# smartIndoor.net
KiCad netlist of a schematic drawn in EAGLE
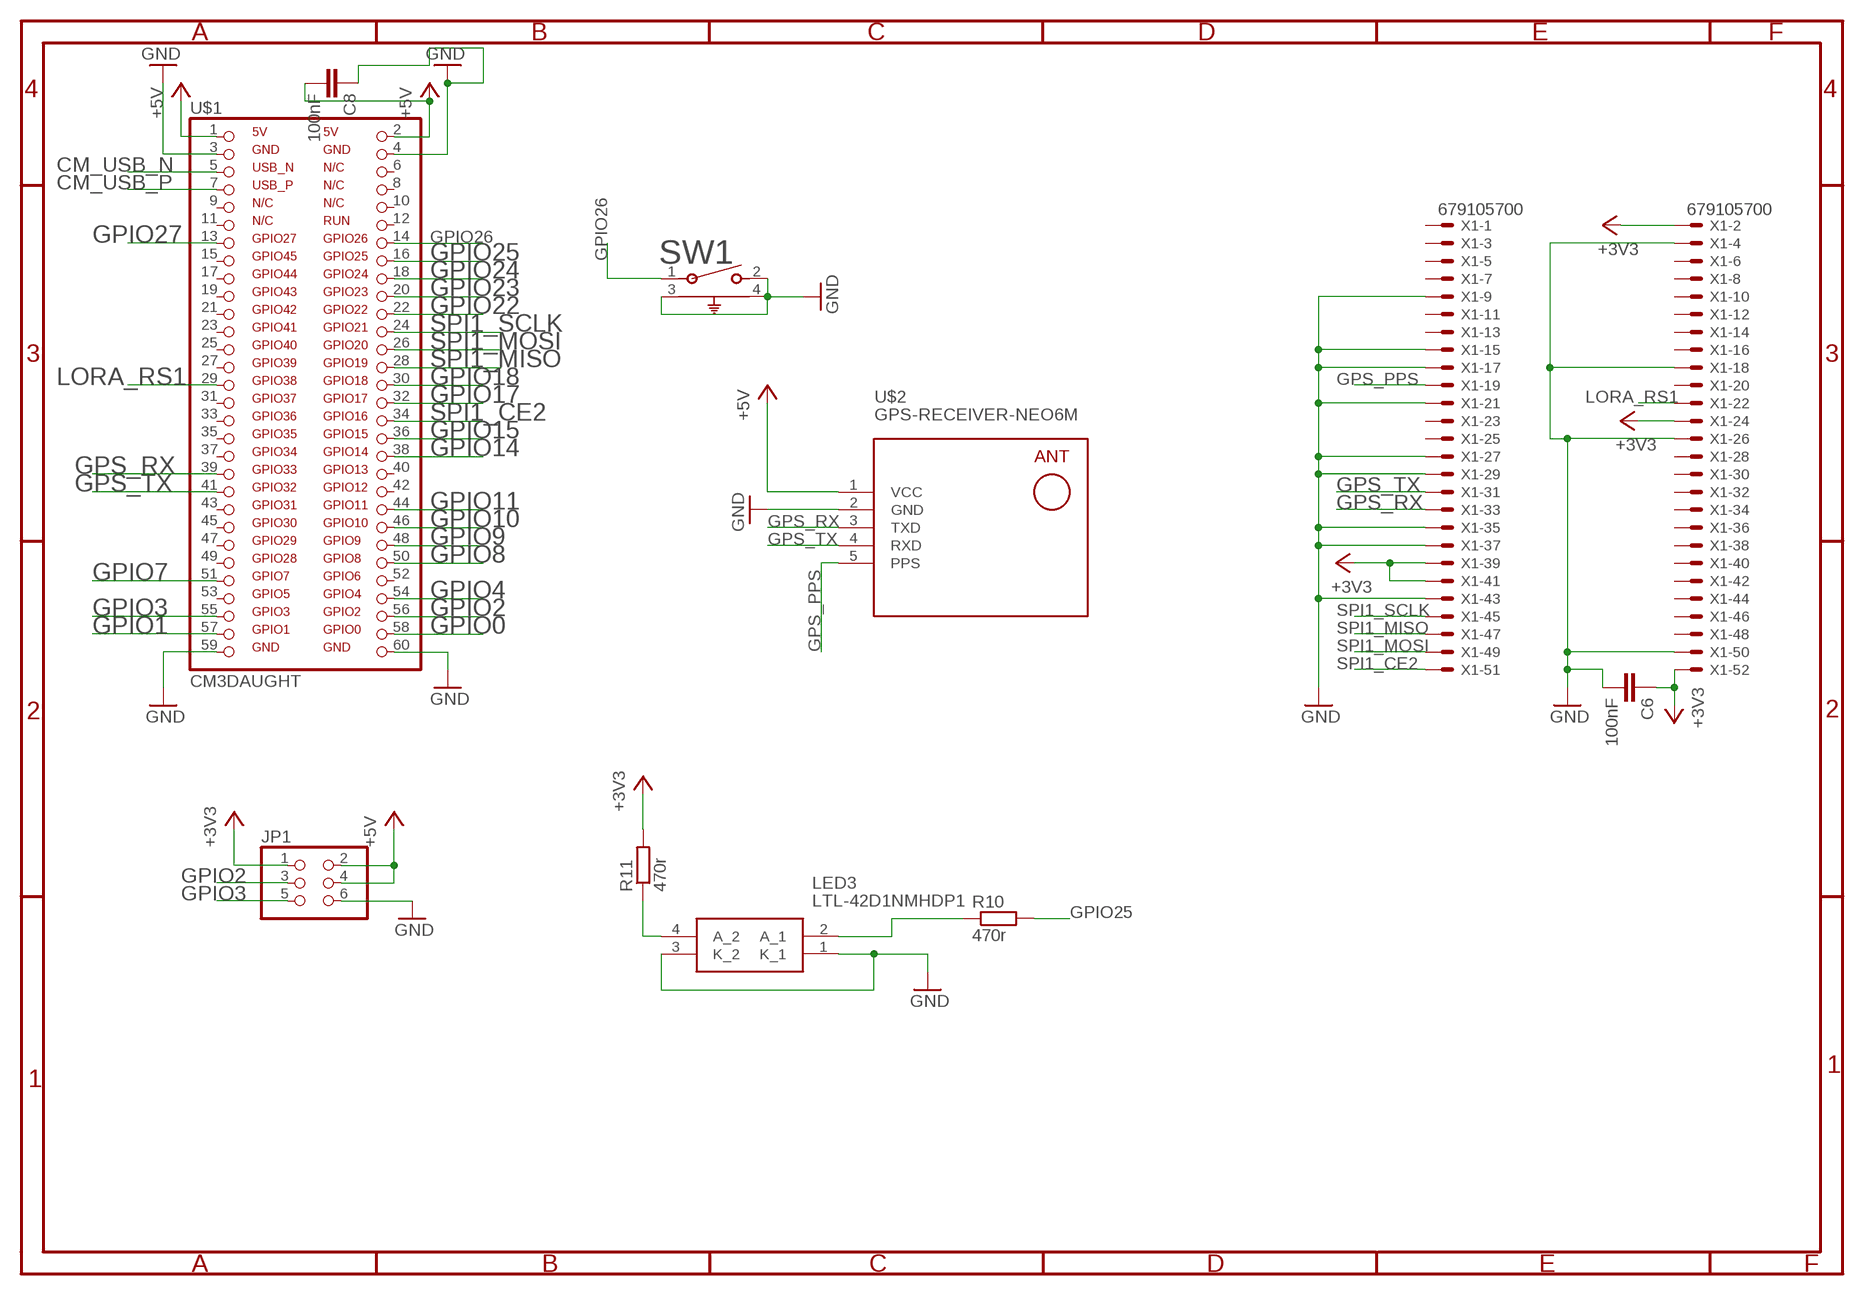
[diagram p0: schematic, sheet 1]
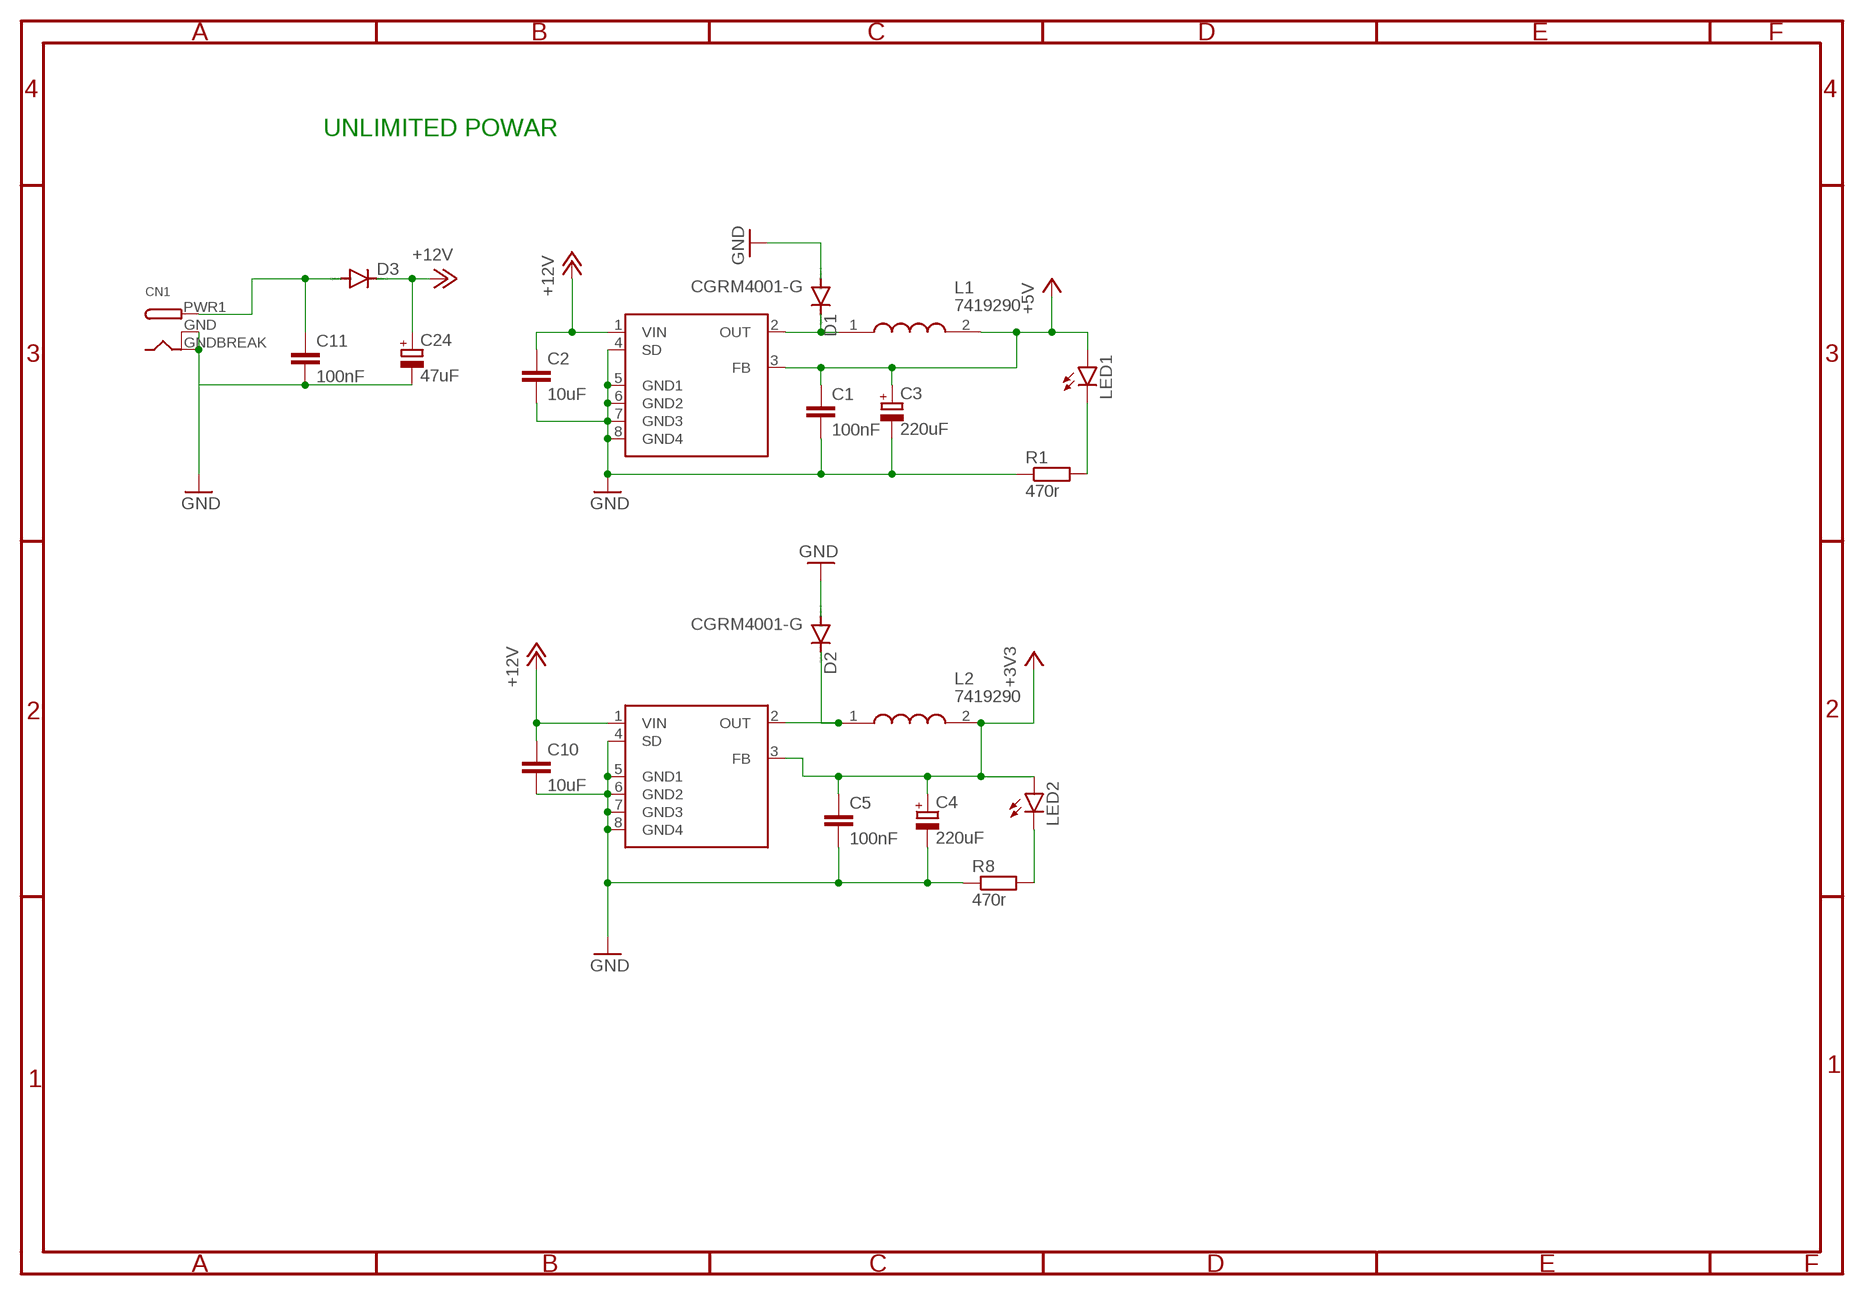
[diagram p1: schematic, sheet 2]
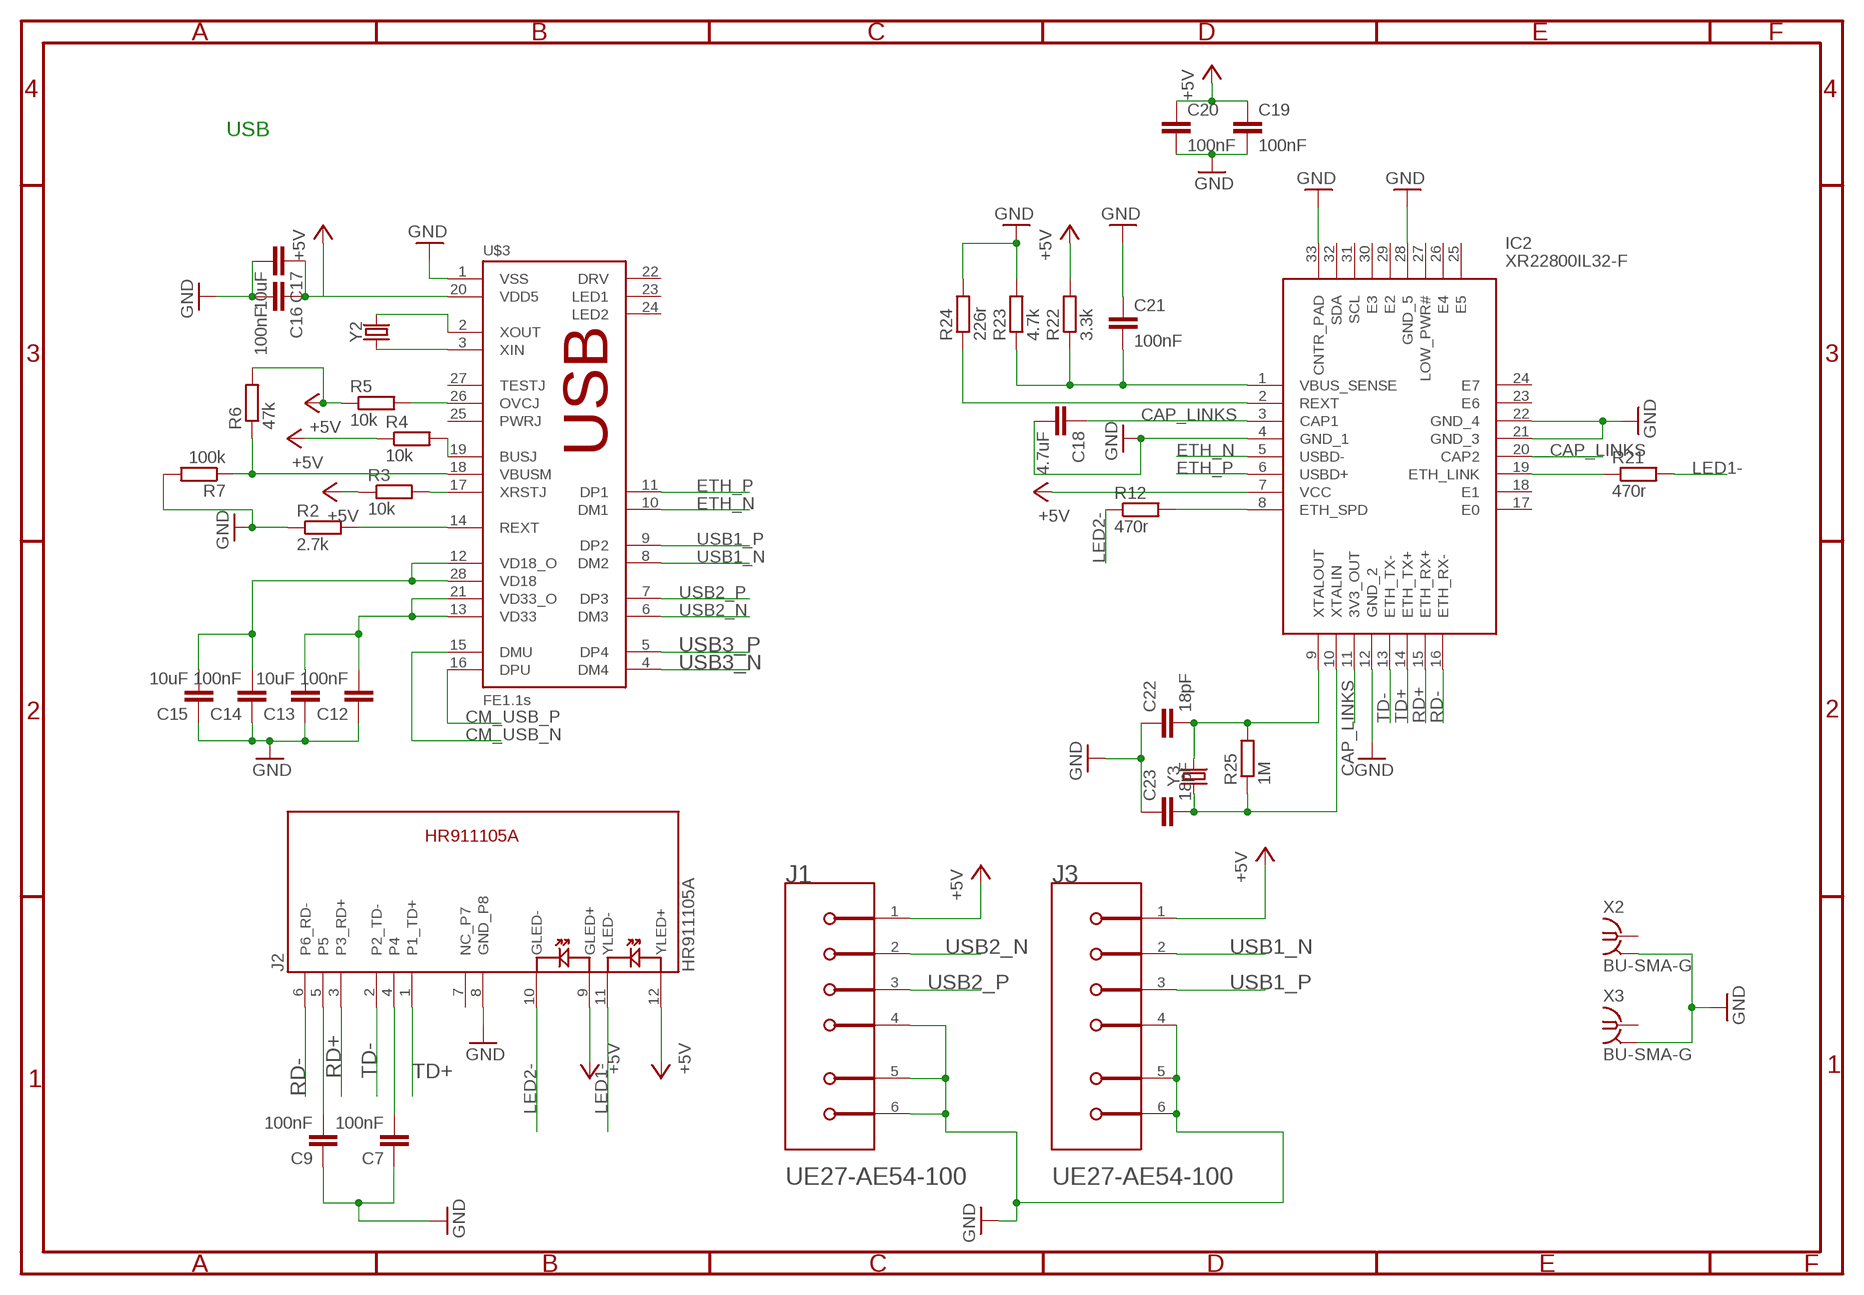
[diagram p2: schematic, sheet 3]

(export (version "E")
  (design (tool "Eeschema 10.0.6"))
  (components
    (comp (ref "C6")
      (value "100nF")
      (footprint "eagle-import:C0603")
      (libsource (lib "eagle-import") (part "C-EUC0603"))
    )
    (comp (ref "C8")
      (value "100nF")
      (footprint "eagle-import:C0603")
      (libsource (lib "eagle-import") (part "C-EUC0603"))
    )
    (comp (ref "JP1")
      (value "PINHD-2X3")
      (footprint "eagle-import:2X03")
      (libsource (lib "eagle-import") (part "PINHD-2X3"))
    )
    (comp (ref "LED3")
      (value "LTL-42D1NMHDP1")
      (footprint "eagle-import:LTL42D1NMHDP1")
      (fields (field (name "MOUSER_PART_NUMBER") "859-LTL-42D1NMHDP1"))
      (libsource (lib "eagle-import") (part "LTL-42D1NMHDP1"))
    )
    (comp (ref "R10")
      (value "470r")
      (footprint "eagle-import:R0603")
      (libsource (lib "eagle-import") (part "R-EU_R0603"))
    )
    (comp (ref "R11")
      (value "470r")
      (footprint "eagle-import:R0603")
      (libsource (lib "eagle-import") (part "R-EU_R0603"))
    )
    (comp (ref "SW1")
      (value "1825027-8")
      (footprint "eagle-import:SW2_1825027-C_TEC")
      (fields (field (name "COPYRIGHT") "Copyright (C) 2016 Accelerated Designs. All rights reserved"))
      (libsource (lib "eagle-import") (part "1825027-8"))
    )
    (comp (ref "U$1")
      (value "CM3DAUGHT")
      (footprint "eagle-import:2X30")
      (libsource (lib "eagle-import") (part "CM3DAUGHT"))
    )
    (comp (ref "U$2")
      (value "GPS-RECEIVER-NEO6M")
      (footprint "eagle-import:GPS-RECEIVER-NEO6M")
      (libsource (lib "eagle-import") (part "GPS-RECEIVER-NEO6M"))
    )
    (comp (ref "X1")
      (value "679105700")
      (footprint "eagle-import:679105700")
      (fields (field (name "MPN") "67910-5700"))
      (libsource (lib "eagle-import") (part "679105700"))
    )
    (comp (ref "C7")
      (value "100nF")
      (footprint "eagle-import:C0603")
      (libsource (lib "eagle-import") (part "C-EUC0603"))
    )
    (comp (ref "C9")
      (value "100nF")
      (footprint "eagle-import:C0603")
      (libsource (lib "eagle-import") (part "C-EUC0603"))
    )
    (comp (ref "C12")
      (value "100nF")
      (footprint "eagle-import:C0603")
      (libsource (lib "eagle-import") (part "C-EUC0603"))
    )
    (comp (ref "C13")
      (value "10uF")
      (footprint "eagle-import:C0603")
      (libsource (lib "eagle-import") (part "C-EUC0603"))
    )
    (comp (ref "C14")
      (value "100nF")
      (footprint "eagle-import:C0603")
      (libsource (lib "eagle-import") (part "C-EUC0603"))
    )
    (comp (ref "C15")
      (value "10uF")
      (footprint "eagle-import:C0603")
      (libsource (lib "eagle-import") (part "C-EUC0603"))
    )
    (comp (ref "C16")
      (value "100nF")
      (footprint "eagle-import:C0603")
      (libsource (lib "eagle-import") (part "C-EUC0603"))
    )
    (comp (ref "C17")
      (value "10uF")
      (footprint "eagle-import:C0603")
      (libsource (lib "eagle-import") (part "C-EUC0603"))
    )
    (comp (ref "C18")
      (value "4.7uF")
      (footprint "eagle-import:C0603")
      (libsource (lib "eagle-import") (part "C-EUC0603"))
    )
    (comp (ref "C19")
      (value "100nF")
      (footprint "eagle-import:C0603")
      (libsource (lib "eagle-import") (part "C-EUC0603"))
    )
    (comp (ref "C20")
      (value "100nF")
      (footprint "eagle-import:C0603")
      (libsource (lib "eagle-import") (part "C-EUC0603"))
    )
    (comp (ref "C21")
      (value "100nF")
      (footprint "eagle-import:C0603")
      (libsource (lib "eagle-import") (part "C-EUC0603"))
    )
    (comp (ref "C22")
      (value "18pF")
      (footprint "eagle-import:C0603")
      (libsource (lib "eagle-import") (part "C-EUC0603"))
    )
    (comp (ref "C23")
      (value "18pF")
      (footprint "eagle-import:C0603")
      (libsource (lib "eagle-import") (part "C-EUC0603"))
    )
    (comp (ref "IC2")
      (value "XR22800IL32-F")
      (footprint "eagle-import:QFN50P500X500X100-33N")
      (fields (field (name "MOUSER_PART_NUMBER") "701-22800IL32-F"))
      (libsource (lib "eagle-import") (part "XR22800IL32-F"))
    )
    (comp (ref "J1")
      (value "AMPHENOL_UE27-AE54-100AMPHENOL_UE27-AE54-100_0_0")
      (footprint "eagle-import:AMPHENOL_UE27-AE54-100_0")
      (fields
        (field (name "DIGIKEY_PART_NUMBER") "UE27AE54100-ND")
        (field (name "MF") "Amphenol")
        (field (name "MOUSER_PART_NUMBER") "523-UE27-AE54-100")
      )
      (libsource (lib "eagle-import") (part "AMPHENOL_UE27-AE54-100AMPHENOL_UE27-AE54-100_0_0"))
    )
    (comp (ref "J2")
      (value "HR911105A")
      (footprint "eagle-import:HR911105A")
      (libsource (lib "eagle-import") (part "HR911105A"))
    )
    (comp (ref "J3")
      (value "AMPHENOL_UE27-AE54-100AMPHENOL_UE27-AE54-100_0_0")
      (footprint "eagle-import:AMPHENOL_UE27-AE54-100_0")
      (fields
        (field (name "DIGIKEY_PART_NUMBER") "UE27AE54100-ND")
        (field (name "MF") "Amphenol")
        (field (name "MOUSER_PART_NUMBER") "523-UE27-AE54-100")
      )
      (libsource (lib "eagle-import") (part "AMPHENOL_UE27-AE54-100AMPHENOL_UE27-AE54-100_0_0"))
    )
    (comp (ref "R2")
      (value "2.7k")
      (footprint "eagle-import:R0603")
      (libsource (lib "eagle-import") (part "R-EU_R0603"))
    )
    (comp (ref "R3")
      (value "10k")
      (footprint "eagle-import:R0603")
      (libsource (lib "eagle-import") (part "R-EU_R0603"))
    )
    (comp (ref "R4")
      (value "10k")
      (footprint "eagle-import:R0603")
      (libsource (lib "eagle-import") (part "R-EU_R0603"))
    )
    (comp (ref "R5")
      (value "10k")
      (footprint "eagle-import:R0603")
      (libsource (lib "eagle-import") (part "R-EU_R0603"))
    )
    (comp (ref "R6")
      (value "47k")
      (footprint "eagle-import:R0603")
      (libsource (lib "eagle-import") (part "R-EU_R0603"))
    )
    (comp (ref "R7")
      (value "100k")
      (footprint "eagle-import:R0603")
      (libsource (lib "eagle-import") (part "R-EU_R0603"))
    )
    (comp (ref "R12")
      (value "470r")
      (footprint "eagle-import:R0603")
      (libsource (lib "eagle-import") (part "R-EU_R0603"))
    )
    (comp (ref "R21")
      (value "470r")
      (footprint "eagle-import:R0603")
      (libsource (lib "eagle-import") (part "R-EU_R0603"))
    )
    (comp (ref "R22")
      (value "3.3k")
      (footprint "eagle-import:R0603")
      (libsource (lib "eagle-import") (part "R-EU_R0603"))
    )
    (comp (ref "R23")
      (value "4.7k")
      (footprint "eagle-import:R0603")
      (libsource (lib "eagle-import") (part "R-EU_R0603"))
    )
    (comp (ref "R24")
      (value "226r")
      (footprint "eagle-import:R0603")
      (libsource (lib "eagle-import") (part "R-EU_R0603"))
    )
    (comp (ref "R25")
      (value "1M")
      (footprint "eagle-import:R0603")
      (libsource (lib "eagle-import") (part "R-EU_R0603"))
    )
    (comp (ref "U$3")
      (value "FE1.1S")
      (footprint "eagle-import:FE1.1S_SSOP-28")
      (libsource (lib "eagle-import") (part "FE1.1S"))
    )
    (comp (ref "X2")
      (value "BU-SMA-G")
      (footprint "eagle-import:BU-SMA-G")
      (libsource (lib "eagle-import") (part "BU-SMA-G"))
    )
    (comp (ref "X3")
      (value "BU-SMA-G")
      (footprint "eagle-import:BU-SMA-G")
      (libsource (lib "eagle-import") (part "BU-SMA-G"))
    )
    (comp (ref "Y2")
      (value "12mHZ")
      (footprint "eagle-import:HC49UP")
      (libsource (lib "eagle-import") (part "CRYSTALSMD-HC49UP"))
    )
    (comp (ref "Y3")
      (value "25Mhz")
      (footprint "eagle-import:HC49UP")
      (libsource (lib "eagle-import") (part "CRYSTALSMD-HC49UP"))
    )
    (comp (ref "C1")
      (value "100nF")
      (footprint "eagle-import:C0603")
      (libsource (lib "eagle-import") (part "C-EUC0603"))
    )
    (comp (ref "C2")
      (value "10uF")
      (footprint "eagle-import:C0603")
      (libsource (lib "eagle-import") (part "C-EUC0603"))
    )
    (comp (ref "C3")
      (value "220uF")
      (footprint "eagle-import:PANASONIC_D")
      (libsource (lib "eagle-import") (part "CPOL-EUD"))
    )
    (comp (ref "C4")
      (value "220uF")
      (footprint "eagle-import:PANASONIC_D")
      (libsource (lib "eagle-import") (part "CPOL-EUD"))
    )
    (comp (ref "C5")
      (value "100nF")
      (footprint "eagle-import:C0603")
      (libsource (lib "eagle-import") (part "C-EUC0603"))
    )
    (comp (ref "C10")
      (value "10uF")
      (footprint "eagle-import:C0603")
      (libsource (lib "eagle-import") (part "C-EUC0603"))
    )
    (comp (ref "C11")
      (value "100nF")
      (footprint "eagle-import:C0603")
      (libsource (lib "eagle-import") (part "C-EUC0603"))
    )
    (comp (ref "C24")
      (value "47uF")
      (footprint "eagle-import:PANASONIC_D")
      (libsource (lib "eagle-import") (part "CPOL-EUD"))
    )
    (comp (ref "CN1")
      (value "DCBARRELSMT")
      (footprint "eagle-import:DCJACK_2MM_SMT")
      (libsource (lib "eagle-import") (part "DCBARRELSMT"))
    )
    (comp (ref "D1")
      (value "CGRM4001-G")
      (footprint "eagle-import:SOD-123_MINI-SMA")
      (libsource (lib "eagle-import") (part "CGRM400-G1"))
    )
    (comp (ref "D2")
      (value "CGRM4001-G")
      (footprint "eagle-import:SOD-123_MINI-SMA")
      (libsource (lib "eagle-import") (part "CGRM400-G1"))
    )
    (comp (ref "D3")
      (value "DIODE-SMB")
      (footprint "eagle-import:SMB")
      (libsource (lib "eagle-import") (part "DIODE-SMB"))
    )
    (comp (ref "L1")
      (value "7419290")
      (footprint "eagle-import:INDPM115100X410N")
      (libsource (lib "eagle-import") (part "7419290"))
    )
    (comp (ref "L2")
      (value "7419290")
      (footprint "eagle-import:INDPM115100X410N")
      (libsource (lib "eagle-import") (part "7419290"))
    )
    (comp (ref "LED1")
      (value "LEDCHIP-LED0603")
      (footprint "eagle-import:CHIP-LED0603")
      (libsource (lib "eagle-import") (part "LEDCHIP-LED0603"))
    )
    (comp (ref "LED2")
      (value "LEDCHIP-LED0603")
      (footprint "eagle-import:CHIP-LED0603")
      (libsource (lib "eagle-import") (part "LEDCHIP-LED0603"))
    )
    (comp (ref "R1")
      (value "470r")
      (footprint "eagle-import:R0603")
      (libsource (lib "eagle-import") (part "R-EU_R0603"))
    )
    (comp (ref "R8")
      (value "470r")
      (footprint "eagle-import:R0603")
      (libsource (lib "eagle-import") (part "R-EU_R0603"))
    )
    (comp (ref "U1")
      (value "AP1509")
      (footprint "eagle-import:SO08")
      (libsource (lib "eagle-import") (part "AP1509"))
    )
    (comp (ref "U2")
      (value "AP1509")
      (footprint "eagle-import:SO08")
      (libsource (lib "eagle-import") (part "AP1509"))
    )
  )
  (nets
    (net (code "1") (name "+3V3") (class "Default")
      (node (ref "C4") (pin "+") (pinfunction "+_+") (pintype "passive"))
      (node (ref "C5") (pin "1") (pinfunction "1_1") (pintype "passive"))
      (node (ref "C6") (pin "1") (pinfunction "1_1") (pintype "passive"))
      (node (ref "JP1") (pin "1") (pinfunction "1_1") (pintype "passive"))
      (node (ref "L2") (pin "2") (pinfunction "2_2") (pintype "bidirectional"))
      (node (ref "LED2") (pin "A") (pinfunction "A_A") (pintype "passive"))
      (node (ref "R11") (pin "2") (pinfunction "2_2") (pintype "passive"))
      (node (ref "U2") (pin "3") (pinfunction "FB_3") (pintype "input"))
      (node (ref "X1") (pin "2") (pinfunction "S_2") (pintype "passive"))
      (node (ref "X1") (pin "24") (pinfunction "S_24") (pintype "passive"))
      (node (ref "X1") (pin "39") (pinfunction "S_39") (pintype "passive"))
      (node (ref "X1") (pin "41") (pinfunction "S_41") (pintype "passive"))
      (node (ref "X1") (pin "52") (pinfunction "S_52") (pintype "passive"))
    )
    (net (code "2") (name "+5V") (class "Default")
      (node (ref "C1") (pin "1") (pinfunction "1_1") (pintype "passive"))
      (node (ref "C16") (pin "1") (pinfunction "1_1") (pintype "passive"))
      (node (ref "C17") (pin "1") (pinfunction "1_1") (pintype "passive"))
      (node (ref "C19") (pin "1") (pinfunction "1_1") (pintype "passive"))
      (node (ref "C20") (pin "1") (pinfunction "1_1") (pintype "passive"))
      (node (ref "C3") (pin "+") (pinfunction "+_+") (pintype "passive"))
      (node (ref "C8") (pin "2") (pinfunction "2_2") (pintype "passive"))
      (node (ref "IC2") (pin "7") (pinfunction "VCC_7") (pintype "bidirectional"))
      (node (ref "J1") (pin "1") (pinfunction "1_1") (pintype "passive"))
      (node (ref "J2") (pin "12") (pinfunction "YLED+_12") (pintype "bidirectional"))
      (node (ref "J2") (pin "9") (pinfunction "GLED+_9") (pintype "bidirectional"))
      (node (ref "J3") (pin "1") (pinfunction "1_1") (pintype "passive"))
      (node (ref "JP1") (pin "2") (pinfunction "2_2") (pintype "passive"))
      (node (ref "JP1") (pin "4") (pinfunction "4_4") (pintype "passive"))
      (node (ref "L1") (pin "2") (pinfunction "2_2") (pintype "bidirectional"))
      (node (ref "LED1") (pin "A") (pinfunction "A_A") (pintype "passive"))
      (node (ref "R22") (pin "2") (pinfunction "2_2") (pintype "passive"))
      (node (ref "R3") (pin "1") (pinfunction "1_1") (pintype "passive"))
      (node (ref "R4") (pin "1") (pinfunction "1_1") (pintype "passive"))
      (node (ref "R5") (pin "1") (pinfunction "1_1") (pintype "passive"))
      (node (ref "R6") (pin "2") (pinfunction "2_2") (pintype "passive"))
      (node (ref "U$1") (pin "1") (pinfunction "5V_1") (pintype "power_in"))
      (node (ref "U$1") (pin "2") (pinfunction "5V_2") (pintype "power_in"))
      (node (ref "U$2") (pin "1") (pinfunction "VCC_1") (pintype "bidirectional"))
      (node (ref "U$3") (pin "20") (pinfunction "VDD5_20") (pintype "bidirectional"))
      (node (ref "U1") (pin "3") (pinfunction "FB_3") (pintype "input"))
    )
    (net (code "3") (name "+12V") (class "Default")
      (node (ref "C10") (pin "1") (pinfunction "1_1") (pintype "passive"))
      (node (ref "C2") (pin "1") (pinfunction "1_1") (pintype "passive"))
      (node (ref "C24") (pin "+") (pinfunction "+_+") (pintype "passive"))
      (node (ref "D3") (pin "C") (pinfunction "C_C") (pintype "passive"))
      (node (ref "U1") (pin "1") (pinfunction "VIN_1") (pintype "power_in"))
      (node (ref "U2") (pin "1") (pinfunction "VIN_1") (pintype "power_in"))
    )
    (net (code "4") (name "CAP_LINKS") (class "Default")
      (node (ref "C18") (pin "1") (pinfunction "1_1") (pintype "passive"))
      (node (ref "IC2") (pin "11") (pinfunction "3V3_OUT_11") (pintype "bidirectional"))
      (node (ref "IC2") (pin "20") (pinfunction "CAP2_20") (pintype "bidirectional"))
      (node (ref "IC2") (pin "3") (pinfunction "CAP1_3") (pintype "bidirectional"))
    )
    (net (code "5") (name "CM_USB_N") (class "Default")
      (node (ref "U$1") (pin "5") (pinfunction "USB_N_5") (pintype "passive"))
      (node (ref "U$3") (pin "15") (pinfunction "DMU_15") (pintype "bidirectional"))
    )
    (net (code "6") (name "CM_USB_P") (class "Default")
      (node (ref "U$1") (pin "7") (pinfunction "USB_P_7") (pintype "passive"))
      (node (ref "U$3") (pin "16") (pinfunction "DPU_16") (pintype "bidirectional"))
    )
    (net (code "7") (name "ETH_N") (class "Default")
      (node (ref "IC2") (pin "5") (pinfunction "USBD-_5") (pintype "bidirectional"))
      (node (ref "U$3") (pin "10") (pinfunction "DM1_10") (pintype "bidirectional"))
    )
    (net (code "8") (name "ETH_P") (class "Default")
      (node (ref "IC2") (pin "6") (pinfunction "USBD+_6") (pintype "bidirectional"))
      (node (ref "U$3") (pin "11") (pinfunction "DP1_11") (pintype "bidirectional"))
    )
    (net (code "9") (name "GND") (class "Default")
      (node (ref "C1") (pin "2") (pinfunction "2_2") (pintype "passive"))
      (node (ref "C10") (pin "2") (pinfunction "2_2") (pintype "passive"))
      (node (ref "C11") (pin "2") (pinfunction "2_2") (pintype "passive"))
      (node (ref "C12") (pin "1") (pinfunction "1_1") (pintype "passive"))
      (node (ref "C13") (pin "1") (pinfunction "1_1") (pintype "passive"))
      (node (ref "C14") (pin "1") (pinfunction "1_1") (pintype "passive"))
      (node (ref "C15") (pin "1") (pinfunction "1_1") (pintype "passive"))
      (node (ref "C16") (pin "2") (pinfunction "2_2") (pintype "passive"))
      (node (ref "C17") (pin "2") (pinfunction "2_2") (pintype "passive"))
      (node (ref "C18") (pin "2") (pinfunction "2_2") (pintype "passive"))
      (node (ref "C19") (pin "2") (pinfunction "2_2") (pintype "passive"))
      (node (ref "C2") (pin "2") (pinfunction "2_2") (pintype "passive"))
      (node (ref "C20") (pin "2") (pinfunction "2_2") (pintype "passive"))
      (node (ref "C21") (pin "1") (pinfunction "1_1") (pintype "passive"))
      (node (ref "C22") (pin "1") (pinfunction "1_1") (pintype "passive"))
      (node (ref "C23") (pin "1") (pinfunction "1_1") (pintype "passive"))
      (node (ref "C24") (pin "-") (pinfunction "-_-") (pintype "passive"))
      (node (ref "C3") (pin "-") (pinfunction "-_-") (pintype "passive"))
      (node (ref "C4") (pin "-") (pinfunction "-_-") (pintype "passive"))
      (node (ref "C5") (pin "2") (pinfunction "2_2") (pintype "passive"))
      (node (ref "C6") (pin "2") (pinfunction "2_2") (pintype "passive"))
      (node (ref "C7") (pin "1") (pinfunction "1_1") (pintype "passive"))
      (node (ref "C8") (pin "1") (pinfunction "1_1") (pintype "passive"))
      (node (ref "C9") (pin "1") (pinfunction "1_1") (pintype "passive"))
      (node (ref "CN1") (pin "GND") (pinfunction "GNDBREAK_GND") (pintype "power_in"))
      (node (ref "CN1") (pin "GNDBREAK") (pinfunction "GND_GNDBREAK") (pintype "power_in"))
      (node (ref "D1") (pin "A") (pinfunction "A_A") (pintype "passive"))
      (node (ref "D2") (pin "A") (pinfunction "A_A") (pintype "passive"))
      (node (ref "IC2") (pin "12") (pinfunction "GND_2_12") (pintype "bidirectional"))
      (node (ref "IC2") (pin "21") (pinfunction "GND_3_21") (pintype "bidirectional"))
      (node (ref "IC2") (pin "22") (pinfunction "GND_4_22") (pintype "bidirectional"))
      (node (ref "IC2") (pin "28") (pinfunction "GND_5_28") (pintype "bidirectional"))
      (node (ref "IC2") (pin "33") (pinfunction "CNTR_PAD_33") (pintype "bidirectional"))
      (node (ref "IC2") (pin "4") (pinfunction "GND_1_4") (pintype "bidirectional"))
      (node (ref "J1") (pin "4") (pinfunction "4_4") (pintype "passive"))
      (node (ref "J1") (pin "5") (pinfunction "MNT_1_5") (pintype "passive"))
      (node (ref "J1") (pin "6") (pinfunction "MNT_2_6") (pintype "passive"))
      (node (ref "J2") (pin "8") (pinfunction "GND_P8_8") (pintype "bidirectional"))
      (node (ref "J3") (pin "4") (pinfunction "4_4") (pintype "passive"))
      (node (ref "J3") (pin "5") (pinfunction "MNT_1_5") (pintype "passive"))
      (node (ref "J3") (pin "6") (pinfunction "MNT_2_6") (pintype "passive"))
      (node (ref "JP1") (pin "6") (pinfunction "6_6") (pintype "passive"))
      (node (ref "LED3") (pin "1") (pinfunction "K_1_1") (pintype "bidirectional"))
      (node (ref "LED3") (pin "3") (pinfunction "K_2_3") (pintype "bidirectional"))
      (node (ref "R1") (pin "1") (pinfunction "1_1") (pintype "passive"))
      (node (ref "R2") (pin "1") (pinfunction "1_1") (pintype "passive"))
      (node (ref "R23") (pin "2") (pinfunction "2_2") (pintype "passive"))
      (node (ref "R24") (pin "2") (pinfunction "2_2") (pintype "passive"))
      (node (ref "R7") (pin "2") (pinfunction "2_2") (pintype "passive"))
      (node (ref "R8") (pin "1") (pinfunction "1_1") (pintype "passive"))
      (node (ref "SW1") (pin "2") (pinfunction "2_2") (pintype "passive"))
      (node (ref "SW1") (pin "3") (pinfunction "3_3") (pintype "passive"))
      (node (ref "SW1") (pin "4") (pinfunction "4_4") (pintype "passive"))
      (node (ref "U$1") (pin "3") (pinfunction "GND_3") (pintype "power_in"))
      (node (ref "U$1") (pin "4") (pinfunction "GND_4") (pintype "power_in"))
      (node (ref "U$1") (pin "59") (pinfunction "GND_59") (pintype "power_in"))
      (node (ref "U$1") (pin "60") (pinfunction "GND_60") (pintype "power_in"))
      (node (ref "U$2") (pin "2") (pinfunction "GND_2") (pintype "bidirectional"))
      (node (ref "U$3") (pin "1") (pinfunction "VSS_1") (pintype "bidirectional"))
      (node (ref "U1") (pin "4") (pinfunction "SD_4") (pintype "input"))
      (node (ref "U1") (pin "5") (pinfunction "GND1_5") (pintype "power_in"))
      (node (ref "U1") (pin "6") (pinfunction "GND2_6") (pintype "power_in"))
      (node (ref "U1") (pin "7") (pinfunction "GND3_7") (pintype "power_in"))
      (node (ref "U1") (pin "8") (pinfunction "GND4_8") (pintype "power_in"))
      (node (ref "U2") (pin "4") (pinfunction "SD_4") (pintype "input"))
      (node (ref "U2") (pin "5") (pinfunction "GND1_5") (pintype "power_in"))
      (node (ref "U2") (pin "6") (pinfunction "GND2_6") (pintype "power_in"))
      (node (ref "U2") (pin "7") (pinfunction "GND3_7") (pintype "power_in"))
      (node (ref "U2") (pin "8") (pinfunction "GND4_8") (pintype "power_in"))
      (node (ref "X1") (pin "15") (pinfunction "S_15") (pintype "passive"))
      (node (ref "X1") (pin "17") (pinfunction "S_17") (pintype "passive"))
      (node (ref "X1") (pin "18") (pinfunction "S_18") (pintype "passive"))
      (node (ref "X1") (pin "21") (pinfunction "S_21") (pintype "passive"))
      (node (ref "X1") (pin "26") (pinfunction "S_26") (pintype "passive"))
      (node (ref "X1") (pin "27") (pinfunction "S_27") (pintype "passive"))
      (node (ref "X1") (pin "29") (pinfunction "S_29") (pintype "passive"))
      (node (ref "X1") (pin "35") (pinfunction "S_35") (pintype "passive"))
      (node (ref "X1") (pin "37") (pinfunction "S_37") (pintype "passive"))
      (node (ref "X1") (pin "4") (pinfunction "S_4") (pintype "passive"))
      (node (ref "X1") (pin "43") (pinfunction "S_43") (pintype "passive"))
      (node (ref "X1") (pin "50") (pinfunction "S_50") (pintype "passive"))
      (node (ref "X1") (pin "9") (pinfunction "S_9") (pintype "passive"))
      (node (ref "X2") (pin "2") (pinfunction "2_2") (pintype "passive"))
      (node (ref "X2") (pin "3") (pinfunction "2_3") (pintype "passive"))
      (node (ref "X2") (pin "4") (pinfunction "2_4") (pintype "passive"))
      (node (ref "X2") (pin "5") (pinfunction "2_5") (pintype "passive"))
      (node (ref "X3") (pin "2") (pinfunction "2_2") (pintype "passive"))
      (node (ref "X3") (pin "3") (pinfunction "2_3") (pintype "passive"))
      (node (ref "X3") (pin "4") (pinfunction "2_4") (pintype "passive"))
      (node (ref "X3") (pin "5") (pinfunction "2_5") (pintype "passive"))
    )
    (net (code "10") (name "GPIO0") (class "Default")
      (node (ref "U$1") (pin "58") (pinfunction "GPIO0_58") (pintype "passive"))
    )
    (net (code "11") (name "GPIO1") (class "Default")
      (node (ref "U$1") (pin "57") (pinfunction "GPIO1_57") (pintype "passive"))
    )
    (net (code "12") (name "GPIO2") (class "Default")
      (node (ref "JP1") (pin "3") (pinfunction "3_3") (pintype "passive"))
      (node (ref "U$1") (pin "56") (pinfunction "GPIO2_56") (pintype "passive"))
    )
    (net (code "13") (name "GPIO3") (class "Default")
      (node (ref "JP1") (pin "5") (pinfunction "5_5") (pintype "passive"))
      (node (ref "U$1") (pin "55") (pinfunction "GPIO3_55") (pintype "passive"))
    )
    (net (code "14") (name "GPIO4") (class "Default")
      (node (ref "U$1") (pin "54") (pinfunction "GPIO4_54") (pintype "passive"))
    )
    (net (code "15") (name "GPIO7") (class "Default")
      (node (ref "U$1") (pin "51") (pinfunction "GPIO7_51") (pintype "passive"))
    )
    (net (code "16") (name "GPIO8") (class "Default")
      (node (ref "U$1") (pin "50") (pinfunction "GPIO8_50") (pintype "passive"))
    )
    (net (code "17") (name "GPIO9") (class "Default")
      (node (ref "U$1") (pin "48") (pinfunction "GPIO9_48") (pintype "passive"))
    )
    (net (code "18") (name "GPIO10") (class "Default")
      (node (ref "U$1") (pin "46") (pinfunction "GPIO10_46") (pintype "passive"))
    )
    (net (code "19") (name "GPIO11") (class "Default")
      (node (ref "U$1") (pin "44") (pinfunction "GPIO11_44") (pintype "passive"))
    )
    (net (code "20") (name "GPIO14") (class "Default")
      (node (ref "U$1") (pin "38") (pinfunction "GPIO14_38") (pintype "passive"))
    )
    (net (code "21") (name "GPIO15") (class "Default")
      (node (ref "U$1") (pin "36") (pinfunction "GPIO15_36") (pintype "passive"))
    )
    (net (code "22") (name "GPIO17") (class "Default")
      (node (ref "U$1") (pin "32") (pinfunction "GPIO17_32") (pintype "passive"))
    )
    (net (code "23") (name "GPIO18") (class "Default")
      (node (ref "U$1") (pin "30") (pinfunction "GPIO18_30") (pintype "passive"))
    )
    (net (code "24") (name "GPIO22") (class "Default")
      (node (ref "U$1") (pin "22") (pinfunction "GPIO22_22") (pintype "passive"))
    )
    (net (code "25") (name "GPIO23") (class "Default")
      (node (ref "U$1") (pin "20") (pinfunction "GPIO23_20") (pintype "passive"))
    )
    (net (code "26") (name "GPIO24") (class "Default")
      (node (ref "U$1") (pin "18") (pinfunction "GPIO24_18") (pintype "passive"))
    )
    (net (code "27") (name "GPIO25") (class "Default")
      (node (ref "R10") (pin "2") (pinfunction "2_2") (pintype "passive"))
      (node (ref "U$1") (pin "16") (pinfunction "GPIO25_16") (pintype "passive"))
    )
    (net (code "28") (name "GPIO26") (class "Default")
      (node (ref "SW1") (pin "1") (pinfunction "1_1") (pintype "passive"))
      (node (ref "U$1") (pin "14") (pinfunction "GPIO26_14") (pintype "passive"))
    )
    (net (code "29") (name "GPIO27") (class "Default")
      (node (ref "U$1") (pin "13") (pinfunction "GPIO27_13") (pintype "passive"))
    )
    (net (code "30") (name "GPS_PPS") (class "Default")
      (node (ref "U$2") (pin "5") (pinfunction "PPS_5") (pintype "power_in"))
      (node (ref "X1") (pin "19") (pinfunction "S_19") (pintype "passive"))
    )
    (net (code "31") (name "GPS_RX") (class "Default")
      (node (ref "U$1") (pin "39") (pinfunction "GPIO33_39") (pintype "passive"))
      (node (ref "U$2") (pin "3") (pinfunction "TXD_3") (pintype "bidirectional"))
      (node (ref "X1") (pin "33") (pinfunction "S_33") (pintype "passive"))
    )
    (net (code "32") (name "GPS_TX") (class "Default")
      (node (ref "U$1") (pin "41") (pinfunction "GPIO32_41") (pintype "passive"))
      (node (ref "U$2") (pin "4") (pinfunction "RXD_4") (pintype "power_in"))
      (node (ref "X1") (pin "31") (pinfunction "S_31") (pintype "passive"))
    )
    (net (code "33") (name "LED1-") (class "Default")
      (node (ref "J2") (pin "11") (pinfunction "YLED-_11") (pintype "bidirectional"))
      (node (ref "R21") (pin "2") (pinfunction "2_2") (pintype "passive"))
    )
    (net (code "34") (name "LED2-") (class "Default")
      (node (ref "J2") (pin "10") (pinfunction "GLED-_10") (pintype "bidirectional"))
      (node (ref "R12") (pin "1") (pinfunction "1_1") (pintype "passive"))
    )
    (net (code "35") (name "LORA_RS1") (class "Default")
      (node (ref "U$1") (pin "29") (pinfunction "GPIO38_29") (pintype "passive"))
      (node (ref "X1") (pin "22") (pinfunction "S_22") (pintype "passive"))
    )
    (net (code "36") (name "Net-(CN1-PWR)") (class "Default")
      (node (ref "C11") (pin "1") (pinfunction "1_1") (pintype "passive"))
      (node (ref "CN1") (pin "PWR1") (pinfunction "PWR_PWR1") (pintype "power_in"))
      (node (ref "D3") (pin "A") (pinfunction "A_A") (pintype "passive"))
    )
    (net (code "37") (name "Net-(IC2-ETH_LINK)") (class "Default")
      (node (ref "IC2") (pin "19") (pinfunction "ETH_LINK_19") (pintype "bidirectional"))
      (node (ref "R21") (pin "1") (pinfunction "1_1") (pintype "passive"))
    )
    (net (code "38") (name "Net-(IC2-ETH_SPD)") (class "Default")
      (node (ref "IC2") (pin "8") (pinfunction "ETH_SPD_8") (pintype "bidirectional"))
      (node (ref "R12") (pin "2") (pinfunction "2_2") (pintype "passive"))
    )
    (net (code "39") (name "Net-(IC2-REXT)") (class "Default")
      (node (ref "IC2") (pin "2") (pinfunction "REXT_2") (pintype "bidirectional"))
      (node (ref "R24") (pin "1") (pinfunction "1_1") (pintype "passive"))
    )
    (net (code "40") (name "Net-(IC2-VBUS_SENSE)") (class "Default")
      (node (ref "C21") (pin "2") (pinfunction "2_2") (pintype "passive"))
      (node (ref "IC2") (pin "1") (pinfunction "VBUS_SENSE_1") (pintype "bidirectional"))
      (node (ref "R22") (pin "1") (pinfunction "1_1") (pintype "passive"))
      (node (ref "R23") (pin "1") (pinfunction "1_1") (pintype "passive"))
    )
    (net (code "41") (name "Net-(IC2-XTALIN)") (class "Default")
      (node (ref "C23") (pin "2") (pinfunction "2_2") (pintype "passive"))
      (node (ref "IC2") (pin "10") (pinfunction "XTALIN_10") (pintype "bidirectional"))
      (node (ref "R25") (pin "1") (pinfunction "1_1") (pintype "passive"))
      (node (ref "Y3") (pin "1") (pinfunction "1_1") (pintype "passive"))
    )
    (net (code "42") (name "Net-(IC2-XTALOUT)") (class "Default")
      (node (ref "C22") (pin "2") (pinfunction "2_2") (pintype "passive"))
      (node (ref "IC2") (pin "9") (pinfunction "XTALOUT_9") (pintype "bidirectional"))
      (node (ref "R25") (pin "2") (pinfunction "2_2") (pintype "passive"))
      (node (ref "Y3") (pin "2") (pinfunction "2_2") (pintype "passive"))
    )
    (net (code "43") (name "Net-(J2-P4)") (class "Default")
      (node (ref "C7") (pin "2") (pinfunction "2_2") (pintype "passive"))
      (node (ref "J2") (pin "4") (pinfunction "P4_4") (pintype "bidirectional"))
    )
    (net (code "44") (name "Net-(J2-P5)") (class "Default")
      (node (ref "C9") (pin "2") (pinfunction "2_2") (pintype "passive"))
      (node (ref "J2") (pin "5") (pinfunction "P5_5") (pintype "bidirectional"))
    )
    (net (code "45") (name "Net-(LED1-PadC)") (class "Default")
      (node (ref "LED1") (pin "C") (pinfunction "C_C") (pintype "passive"))
      (node (ref "R1") (pin "2") (pinfunction "2_2") (pintype "passive"))
    )
    (net (code "46") (name "Net-(LED2-PadC)") (class "Default")
      (node (ref "LED2") (pin "C") (pinfunction "C_C") (pintype "passive"))
      (node (ref "R8") (pin "2") (pinfunction "2_2") (pintype "passive"))
    )
    (net (code "47") (name "Net-(LED3-A_1)") (class "Default")
      (node (ref "LED3") (pin "2") (pinfunction "A_1_2") (pintype "bidirectional"))
      (node (ref "R10") (pin "1") (pinfunction "1_1") (pintype "passive"))
    )
    (net (code "48") (name "Net-(LED3-A_2)") (class "Default")
      (node (ref "LED3") (pin "4") (pinfunction "A_2_4") (pintype "bidirectional"))
      (node (ref "R11") (pin "1") (pinfunction "1_1") (pintype "passive"))
    )
    (net (code "49") (name "Net-(U$3-BUSJ)") (class "Default")
      (node (ref "R4") (pin "2") (pinfunction "2_2") (pintype "passive"))
      (node (ref "U$3") (pin "19") (pinfunction "BUSJ_19") (pintype "bidirectional"))
    )
    (net (code "50") (name "Net-(U$3-OVCJ)") (class "Default")
      (node (ref "R5") (pin "2") (pinfunction "2_2") (pintype "passive"))
      (node (ref "U$3") (pin "26") (pinfunction "OVCJ_26") (pintype "bidirectional"))
    )
    (net (code "51") (name "Net-(U$3-REXT)") (class "Default")
      (node (ref "R2") (pin "2") (pinfunction "2_2") (pintype "passive"))
      (node (ref "U$3") (pin "14") (pinfunction "REXT_14") (pintype "bidirectional"))
    )
    (net (code "52") (name "Net-(U$3-VBUSM)") (class "Default")
      (node (ref "R6") (pin "1") (pinfunction "1_1") (pintype "passive"))
      (node (ref "R7") (pin "1") (pinfunction "1_1") (pintype "passive"))
      (node (ref "U$3") (pin "18") (pinfunction "VBUSM_18") (pintype "bidirectional"))
    )
    (net (code "53") (name "Net-(U$3-VD18)") (class "Default")
      (node (ref "C14") (pin "2") (pinfunction "2_2") (pintype "passive"))
      (node (ref "C15") (pin "2") (pinfunction "2_2") (pintype "passive"))
      (node (ref "U$3") (pin "12") (pinfunction "VD18_O_12") (pintype "bidirectional"))
      (node (ref "U$3") (pin "28") (pinfunction "VD18_28") (pintype "bidirectional"))
    )
    (net (code "54") (name "Net-(U$3-VD33)") (class "Default")
      (node (ref "C12") (pin "2") (pinfunction "2_2") (pintype "passive"))
      (node (ref "C13") (pin "2") (pinfunction "2_2") (pintype "passive"))
      (node (ref "U$3") (pin "13") (pinfunction "VD33_13") (pintype "bidirectional"))
      (node (ref "U$3") (pin "21") (pinfunction "VD33_O_21") (pintype "bidirectional"))
    )
    (net (code "55") (name "Net-(U$3-XIN)") (class "Default")
      (node (ref "U$3") (pin "3") (pinfunction "XIN_3") (pintype "bidirectional"))
      (node (ref "Y2") (pin "1") (pinfunction "1_1") (pintype "passive"))
    )
    (net (code "56") (name "Net-(U$3-XOUT)") (class "Default")
      (node (ref "U$3") (pin "2") (pinfunction "XOUT_2") (pintype "bidirectional"))
      (node (ref "Y2") (pin "2") (pinfunction "2_2") (pintype "passive"))
    )
    (net (code "57") (name "Net-(U$3-XRSTJ)") (class "Default")
      (node (ref "R3") (pin "2") (pinfunction "2_2") (pintype "passive"))
      (node (ref "U$3") (pin "17") (pinfunction "XRSTJ_17") (pintype "bidirectional"))
    )
    (net (code "58") (name "Net-(U1-OUT)") (class "Default")
      (node (ref "D1") (pin "C") (pinfunction "C_C") (pintype "passive"))
      (node (ref "L1") (pin "1") (pinfunction "1_1") (pintype "bidirectional"))
      (node (ref "U1") (pin "2") (pinfunction "OUT_2") (pintype "output"))
    )
    (net (code "59") (name "Net-(U2-OUT)") (class "Default")
      (node (ref "D2") (pin "C") (pinfunction "C_C") (pintype "passive"))
      (node (ref "L2") (pin "1") (pinfunction "1_1") (pintype "bidirectional"))
      (node (ref "U2") (pin "2") (pinfunction "OUT_2") (pintype "output"))
    )
    (net (code "60") (name "RD+") (class "Default")
      (node (ref "IC2") (pin "15") (pinfunction "ETH_RX+_15") (pintype "bidirectional"))
      (node (ref "J2") (pin "3") (pinfunction "P3_RD+_3") (pintype "bidirectional"))
    )
    (net (code "61") (name "RD-") (class "Default")
      (node (ref "IC2") (pin "16") (pinfunction "ETH_RX-_16") (pintype "bidirectional"))
      (node (ref "J2") (pin "6") (pinfunction "P6_RD-_6") (pintype "bidirectional"))
    )
    (net (code "62") (name "SPI1_CE2") (class "Default")
      (node (ref "U$1") (pin "34") (pinfunction "GPIO16_34") (pintype "passive"))
      (node (ref "X1") (pin "51") (pinfunction "S_51") (pintype "passive"))
    )
    (net (code "63") (name "SPI1_MISO") (class "Default")
      (node (ref "U$1") (pin "28") (pinfunction "GPIO19_28") (pintype "passive"))
      (node (ref "X1") (pin "47") (pinfunction "S_47") (pintype "passive"))
    )
    (net (code "64") (name "SPI1_MOSI") (class "Default")
      (node (ref "U$1") (pin "26") (pinfunction "GPIO20_26") (pintype "passive"))
      (node (ref "X1") (pin "49") (pinfunction "S_49") (pintype "passive"))
    )
    (net (code "65") (name "SPI1_SCLK") (class "Default")
      (node (ref "U$1") (pin "24") (pinfunction "GPIO21_24") (pintype "passive"))
      (node (ref "X1") (pin "45") (pinfunction "S_45") (pintype "passive"))
    )
    (net (code "66") (name "TD+") (class "Default")
      (node (ref "IC2") (pin "14") (pinfunction "ETH_TX+_14") (pintype "bidirectional"))
      (node (ref "J2") (pin "1") (pinfunction "P1_TD+_1") (pintype "bidirectional"))
    )
    (net (code "67") (name "TD-") (class "Default")
      (node (ref "IC2") (pin "13") (pinfunction "ETH_TX-_13") (pintype "bidirectional"))
      (node (ref "J2") (pin "2") (pinfunction "P2_TD-_2") (pintype "bidirectional"))
    )
    (net (code "68") (name "USB1_N") (class "Default")
      (node (ref "J3") (pin "2") (pinfunction "2_2") (pintype "passive"))
      (node (ref "U$3") (pin "8") (pinfunction "DM2_8") (pintype "bidirectional"))
    )
    (net (code "69") (name "USB1_P") (class "Default")
      (node (ref "J3") (pin "3") (pinfunction "3_3") (pintype "passive"))
      (node (ref "U$3") (pin "9") (pinfunction "DP2_9") (pintype "bidirectional"))
    )
    (net (code "70") (name "USB2_N") (class "Default")
      (node (ref "J1") (pin "2") (pinfunction "2_2") (pintype "passive"))
      (node (ref "U$3") (pin "6") (pinfunction "DM3_6") (pintype "bidirectional"))
    )
    (net (code "71") (name "USB2_P") (class "Default")
      (node (ref "J1") (pin "3") (pinfunction "3_3") (pintype "passive"))
      (node (ref "U$3") (pin "7") (pinfunction "DP3_7") (pintype "bidirectional"))
    )
    (net (code "72") (name "USB3_N") (class "Default")
      (node (ref "U$3") (pin "4") (pinfunction "DM4_4") (pintype "bidirectional"))
    )
    (net (code "73") (name "USB3_P") (class "Default")
      (node (ref "U$3") (pin "5") (pinfunction "DP4_5") (pintype "bidirectional"))
    )
    (net (code "74") (name "unconnected-(IC2-E0-Pad17)") (class "Default")
      (node (ref "IC2") (pin "17") (pinfunction "E0_17") (pintype "bidirectional"))
    )
    (net (code "75") (name "unconnected-(IC2-E1-Pad18)") (class "Default")
      (node (ref "IC2") (pin "18") (pinfunction "E1_18") (pintype "bidirectional"))
    )
    (net (code "76") (name "unconnected-(IC2-E2-Pad29)") (class "Default")
      (node (ref "IC2") (pin "29") (pinfunction "E2_29") (pintype "bidirectional"))
    )
    (net (code "77") (name "unconnected-(IC2-E3-Pad30)") (class "Default")
      (node (ref "IC2") (pin "30") (pinfunction "E3_30") (pintype "bidirectional"))
    )
    (net (code "78") (name "unconnected-(IC2-E4-Pad26)") (class "Default")
      (node (ref "IC2") (pin "26") (pinfunction "E4_26") (pintype "bidirectional"))
    )
    (net (code "79") (name "unconnected-(IC2-E5-Pad25)") (class "Default")
      (node (ref "IC2") (pin "25") (pinfunction "E5_25") (pintype "bidirectional"))
    )
    (net (code "80") (name "unconnected-(IC2-E6-Pad23)") (class "Default")
      (node (ref "IC2") (pin "23") (pinfunction "E6_23") (pintype "bidirectional"))
    )
    (net (code "81") (name "unconnected-(IC2-E7-Pad24)") (class "Default")
      (node (ref "IC2") (pin "24") (pinfunction "E7_24") (pintype "bidirectional"))
    )
    (net (code "82") (name "unconnected-(IC2-LOW_PWR#-Pad27)") (class "Default")
      (node (ref "IC2") (pin "27") (pinfunction "LOW_PWR#_27") (pintype "bidirectional"))
    )
    (net (code "83") (name "unconnected-(IC2-SCL-Pad31)") (class "Default")
      (node (ref "IC2") (pin "31") (pinfunction "SCL_31") (pintype "bidirectional"))
    )
    (net (code "84") (name "unconnected-(IC2-SDA-Pad32)") (class "Default")
      (node (ref "IC2") (pin "32") (pinfunction "SDA_32") (pintype "bidirectional"))
    )
    (net (code "85") (name "unconnected-(J2-NC_P7-Pad7)") (class "Default")
      (node (ref "J2") (pin "7") (pinfunction "NC_P7_7") (pintype "bidirectional"))
    )
    (net (code "86") (name "unconnected-(U$1-GPIO5-Pad53)") (class "Default")
      (node (ref "U$1") (pin "53") (pinfunction "GPIO5_53") (pintype "passive"))
    )
    (net (code "87") (name "unconnected-(U$1-GPIO6-Pad52)") (class "Default")
      (node (ref "U$1") (pin "52") (pinfunction "GPIO6_52") (pintype "passive"))
    )
    (net (code "88") (name "unconnected-(U$1-GPIO12-Pad42)") (class "Default")
      (node (ref "U$1") (pin "42") (pinfunction "GPIO12_42") (pintype "passive"))
    )
    (net (code "89") (name "unconnected-(U$1-GPIO13-Pad40)") (class "Default")
      (node (ref "U$1") (pin "40") (pinfunction "GPIO13_40") (pintype "passive"))
    )
    (net (code "90") (name "unconnected-(U$1-GPIO28-Pad49)") (class "Default")
      (node (ref "U$1") (pin "49") (pinfunction "GPIO28_49") (pintype "passive"))
    )
    (net (code "91") (name "unconnected-(U$1-GPIO29-Pad47)") (class "Default")
      (node (ref "U$1") (pin "47") (pinfunction "GPIO29_47") (pintype "passive"))
    )
    (net (code "92") (name "unconnected-(U$1-GPIO30-Pad45)") (class "Default")
      (node (ref "U$1") (pin "45") (pinfunction "GPIO30_45") (pintype "passive"))
    )
    (net (code "93") (name "unconnected-(U$1-GPIO31-Pad43)") (class "Default")
      (node (ref "U$1") (pin "43") (pinfunction "GPIO31_43") (pintype "passive"))
    )
    (net (code "94") (name "unconnected-(U$1-GPIO34-Pad37)") (class "Default")
      (node (ref "U$1") (pin "37") (pinfunction "GPIO34_37") (pintype "passive"))
    )
    (net (code "95") (name "unconnected-(U$1-GPIO35-Pad35)") (class "Default")
      (node (ref "U$1") (pin "35") (pinfunction "GPIO35_35") (pintype "passive"))
    )
    (net (code "96") (name "unconnected-(U$1-GPIO36-Pad33)") (class "Default")
      (node (ref "U$1") (pin "33") (pinfunction "GPIO36_33") (pintype "passive"))
    )
    (net (code "97") (name "unconnected-(U$1-GPIO37-Pad31)") (class "Default")
      (node (ref "U$1") (pin "31") (pinfunction "GPIO37_31") (pintype "passive"))
    )
    (net (code "98") (name "unconnected-(U$1-GPIO39-Pad27)") (class "Default")
      (node (ref "U$1") (pin "27") (pinfunction "GPIO39_27") (pintype "passive"))
    )
    (net (code "99") (name "unconnected-(U$1-GPIO40-Pad25)") (class "Default")
      (node (ref "U$1") (pin "25") (pinfunction "GPIO40_25") (pintype "passive"))
    )
    (net (code "100") (name "unconnected-(U$1-GPIO41-Pad23)") (class "Default")
      (node (ref "U$1") (pin "23") (pinfunction "GPIO41_23") (pintype "passive"))
    )
    (net (code "101") (name "unconnected-(U$1-GPIO42-Pad21)") (class "Default")
      (node (ref "U$1") (pin "21") (pinfunction "GPIO42_21") (pintype "passive"))
    )
    (net (code "102") (name "unconnected-(U$1-GPIO43-Pad19)") (class "Default")
      (node (ref "U$1") (pin "19") (pinfunction "GPIO43_19") (pintype "passive"))
    )
    (net (code "103") (name "unconnected-(U$1-GPIO44-Pad17)") (class "Default")
      (node (ref "U$1") (pin "17") (pinfunction "GPIO44_17") (pintype "passive"))
    )
    (net (code "104") (name "unconnected-(U$1-GPIO45-Pad15)") (class "Default")
      (node (ref "U$1") (pin "15") (pinfunction "GPIO45_15") (pintype "passive"))
    )
    (net (code "105") (name "unconnected-(U$1-Pad6)") (class "Default")
      (node (ref "U$1") (pin "6") (pinfunction "6_6") (pintype "passive"))
    )
    (net (code "106") (name "unconnected-(U$1-Pad8)") (class "Default")
      (node (ref "U$1") (pin "8") (pinfunction "8_8") (pintype "passive"))
    )
    (net (code "107") (name "unconnected-(U$1-Pad9)") (class "Default")
      (node (ref "U$1") (pin "9") (pinfunction "9_9") (pintype "passive"))
    )
    (net (code "108") (name "unconnected-(U$1-Pad10)") (class "Default")
      (node (ref "U$1") (pin "10") (pinfunction "10_10") (pintype "passive"))
    )
    (net (code "109") (name "unconnected-(U$1-Pad11)") (class "Default")
      (node (ref "U$1") (pin "11") (pinfunction "11_11") (pintype "passive"))
    )
    (net (code "110") (name "unconnected-(U$1-Pad12)") (class "Default")
      (node (ref "U$1") (pin "12") (pinfunction "12_12") (pintype "passive"))
    )
    (net (code "111") (name "unconnected-(U$3-DRV-Pad22)") (class "Default")
      (node (ref "U$3") (pin "22") (pinfunction "DRV_22") (pintype "bidirectional"))
    )
    (net (code "112") (name "unconnected-(U$3-LED1-Pad23)") (class "Default")
      (node (ref "U$3") (pin "23") (pinfunction "LED1_23") (pintype "bidirectional"))
    )
    (net (code "113") (name "unconnected-(U$3-LED2-Pad24)") (class "Default")
      (node (ref "U$3") (pin "24") (pinfunction "LED2_24") (pintype "bidirectional"))
    )
    (net (code "114") (name "unconnected-(U$3-PWRJ-Pad25)") (class "Default")
      (node (ref "U$3") (pin "25") (pinfunction "PWRJ_25") (pintype "bidirectional"))
    )
    (net (code "115") (name "unconnected-(U$3-TESTJ-Pad27)") (class "Default")
      (node (ref "U$3") (pin "27") (pinfunction "TESTJ_27") (pintype "bidirectional"))
    )
    (net (code "116") (name "unconnected-(X1A-S-Pad1)") (class "Default")
      (node (ref "X1") (pin "1") (pinfunction "S_1") (pintype "passive"))
    )
    (net (code "117") (name "unconnected-(X1AB-S-Pad34)") (class "Default")
      (node (ref "X1") (pin "34") (pinfunction "S_34") (pintype "passive"))
    )
    (net (code "118") (name "unconnected-(X1AD-S-Pad36)") (class "Default")
      (node (ref "X1") (pin "36") (pinfunction "S_36") (pintype "passive"))
    )
    (net (code "119") (name "unconnected-(X1AF-S-Pad38)") (class "Default")
      (node (ref "X1") (pin "38") (pinfunction "S_38") (pintype "passive"))
    )
    (net (code "120") (name "unconnected-(X1AI-S-Pad40)") (class "Default")
      (node (ref "X1") (pin "40") (pinfunction "S_40") (pintype "passive"))
    )
    (net (code "121") (name "unconnected-(X1AK-S-Pad42)") (class "Default")
      (node (ref "X1") (pin "42") (pinfunction "S_42") (pintype "passive"))
    )
    (net (code "122") (name "unconnected-(X1AM-S-Pad44)") (class "Default")
      (node (ref "X1") (pin "44") (pinfunction "S_44") (pintype "passive"))
    )
    (net (code "123") (name "unconnected-(X1AO-S-Pad46)") (class "Default")
      (node (ref "X1") (pin "46") (pinfunction "S_46") (pintype "passive"))
    )
    (net (code "124") (name "unconnected-(X1AQ-S-Pad48)") (class "Default")
      (node (ref "X1") (pin "48") (pinfunction "S_48") (pintype "passive"))
    )
    (net (code "125") (name "unconnected-(X1AS-S-Pad5)") (class "Default")
      (node (ref "X1") (pin "5") (pinfunction "S_5") (pintype "passive"))
    )
    (net (code "126") (name "unconnected-(X1AW-S-Pad6)") (class "Default")
      (node (ref "X1") (pin "6") (pinfunction "S_6") (pintype "passive"))
    )
    (net (code "127") (name "unconnected-(X1AX-S-Pad7)") (class "Default")
      (node (ref "X1") (pin "7") (pinfunction "S_7") (pintype "passive"))
    )
    (net (code "128") (name "unconnected-(X1AY-S-Pad8)") (class "Default")
      (node (ref "X1") (pin "8") (pinfunction "S_8") (pintype "passive"))
    )
    (net (code "129") (name "unconnected-(X1B-S-Pad10)") (class "Default")
      (node (ref "X1") (pin "10") (pinfunction "S_10") (pintype "passive"))
    )
    (net (code "130") (name "unconnected-(X1C-S-Pad11)") (class "Default")
      (node (ref "X1") (pin "11") (pinfunction "S_11") (pintype "passive"))
    )
    (net (code "131") (name "unconnected-(X1D-S-Pad12)") (class "Default")
      (node (ref "X1") (pin "12") (pinfunction "S_12") (pintype "passive"))
    )
    (net (code "132") (name "unconnected-(X1E-S-Pad13)") (class "Default")
      (node (ref "X1") (pin "13") (pinfunction "S_13") (pintype "passive"))
    )
    (net (code "133") (name "unconnected-(X1F-S-Pad14)") (class "Default")
      (node (ref "X1") (pin "14") (pinfunction "S_14") (pintype "passive"))
    )
    (net (code "134") (name "unconnected-(X1H-S-Pad16)") (class "Default")
      (node (ref "X1") (pin "16") (pinfunction "S_16") (pintype "passive"))
    )
    (net (code "135") (name "unconnected-(X1M-S-Pad20)") (class "Default")
      (node (ref "X1") (pin "20") (pinfunction "S_20") (pintype "passive"))
    )
    (net (code "136") (name "unconnected-(X1P-S-Pad23)") (class "Default")
      (node (ref "X1") (pin "23") (pinfunction "S_23") (pintype "passive"))
    )
    (net (code "137") (name "unconnected-(X1R-S-Pad25)") (class "Default")
      (node (ref "X1") (pin "25") (pinfunction "S_25") (pintype "passive"))
    )
    (net (code "138") (name "unconnected-(X1U-S-Pad28)") (class "Default")
      (node (ref "X1") (pin "28") (pinfunction "S_28") (pintype "passive"))
    )
    (net (code "139") (name "unconnected-(X1W-S-Pad3)") (class "Default")
      (node (ref "X1") (pin "3") (pinfunction "S_3") (pintype "passive"))
    )
    (net (code "140") (name "unconnected-(X1X-S-Pad30)") (class "Default")
      (node (ref "X1") (pin "30") (pinfunction "S_30") (pintype "passive"))
    )
    (net (code "141") (name "unconnected-(X1Z-S-Pad32)") (class "Default")
      (node (ref "X1") (pin "32") (pinfunction "S_32") (pintype "passive"))
    )
    (net (code "142") (name "unconnected-(X2-Pad1)") (class "Default")
      (node (ref "X2") (pin "1") (pinfunction "1_1") (pintype "passive"))
    )
    (net (code "143") (name "unconnected-(X3-Pad1)") (class "Default")
      (node (ref "X3") (pin "1") (pinfunction "1_1") (pintype "passive"))
    )
  )
)
